# lipo-supply.net
KiCad netlist of a schematic drawn in Altium Designer
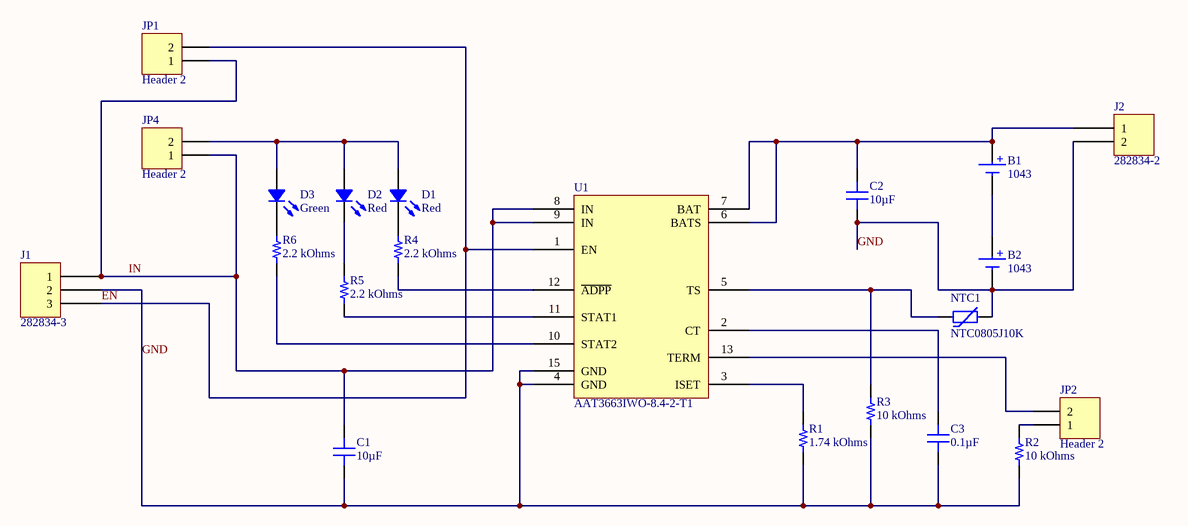
[diagram p0: lipo-supply.SchDoc]

(export (version "E")
  (design (tool "Eeschema 10.0.6"))
  (components
    (comp (ref "B1")
      (value "1043")
      (footprint "KEYSTONE 1043")
      (description "BATTERY HOLDER 18650 PC PIN")
      (fields (field (name "MANUFACTURER") "Keystone Electronics"))
      (libsource (lib "Celestial Altium Library - altium_library") (part "Keystone 1043"))
    )
    (comp (ref "B2")
      (value "1043")
      (footprint "KEYSTONE 1043")
      (description "BATTERY HOLDER 18650 PC PIN")
      (fields (field (name "MANUFACTURER") "Keystone Electronics"))
      (libsource (lib "Celestial Altium Library - altium_library") (part "Keystone 1043"))
    )
    (comp (ref "C1")
      (value "10µF")
      (footprint "CAP 1210_3225 - 2.8MM")
      (description "CAP CER 10UF 25V X7R 1210 EPOXY")
      (fields
        (field (name "PART NUMBER") "GCG32ER71E106KA12L")
        (field (name "MANUFACTURER") "Murata Electronics")
      )
      (libsource (lib "Celestial Altium Library - altium_library") (part "Capacitor"))
    )
    (comp (ref "C2")
      (value "10µF")
      (footprint "CAP 0805_2012")
      (description "CAP CER 10UF 16V X7R 0805")
      (fields (field (name "PART NUMBER") "EMK212BB7106MG-T") (field (name "MANUFACTURER") "Taiyo Yuden"))
      (libsource (lib "Celestial Altium Library - altium_library") (part "Capacitor"))
    )
    (comp (ref "C3")
      (value "0.1µF")
      (footprint "CAP 0805_2012")
      (description "CAP CER 0.1UF 16V X7R 0805")
      (fields
        (field (name "PART NUMBER") "0805B104K160CT")
        (field (name "MANUFACTURER") "Walsin Technology Corporation")
      )
      (libsource (lib "Celestial Altium Library - altium_library") (part "Capacitor"))
    )
    (comp (ref "D1")
      (value "Red")
      (footprint "LED 0805_2012 RED")
      (description "LED RED 0805 SMD")
      (fields (field (name "PART NUMBER") "5990110007F") (field (name "MANUFACTURER") "Dialight"))
      (libsource (lib "Celestial Altium Library - altium_library") (part "LED"))
    )
    (comp (ref "D2")
      (value "Red")
      (footprint "LED 0805_2012 RED")
      (description "LED RED 0805 SMD")
      (fields (field (name "PART NUMBER") "5990110007F") (field (name "MANUFACTURER") "Dialight"))
      (libsource (lib "Celestial Altium Library - altium_library") (part "LED"))
    )
    (comp (ref "D3")
      (value "Green")
      (footprint "LED 0805_2012 GREEN")
      (description "LED GREEN 0805 SMD")
      (fields (field (name "PART NUMBER") "5975316507F") (field (name "MANUFACTURER") "Dialight"))
      (libsource (lib "Celestial Altium Library - altium_library") (part "LED"))
    )
    (comp (ref "J1")
      (value "282834-3")
      (footprint "TE 282834-3")
      (description "TERM BLK 3P SIDE ENT 2.54MM PCB")
      (fields (field (name "MANUFACTURER") "TE Connectivity AMP Connectors") (field (name "VOLTAGE") "150V"))
      (libsource (lib "Celestial Altium Library - altium_library") (part "3 Pin"))
    )
    (comp (ref "J2")
      (value "282834-2")
      (footprint "TE 282834-2")
      (description "TERM BLK 2P SIDE ENT 2.54MM PCB")
      (fields (field (name "MANUFACTURER") "TE Connectivity AMP Connectors") (field (name "VOLTAGE") "150V"))
      (libsource (lib "Celestial Altium Library - altium_library") (part "2 Pin"))
    )
    (comp (ref "JP1")
      (value "Header 2")
      (footprint "HDR1X2")
      (description "Header, 2-Pin")
      (fields (field (name "PUBLISHER") "Altium Limited"))
      (libsource (lib "") (part "Header 2_1"))
    )
    (comp (ref "JP2")
      (value "Header 2")
      (footprint "HDR1X2")
      (description "Header, 2-Pin")
      (fields (field (name "PUBLISHER") "Altium Limited"))
      (libsource (lib "Miscellaneous Connectors") (part "Header 2"))
    )
    (comp (ref "JP4")
      (value "Header 2")
      (footprint "HDR1X2")
      (description "Header, 2-Pin")
      (fields (field (name "PUBLISHER") "Altium Limited"))
      (libsource (lib "") (part "Header 2_1"))
    )
    (comp (ref "NTC1")
      (value "NTC0805J10K")
      (footprint "NTC 0805_2012")
      (description "THERMISTOR NTC 10KOHM 0805")
      (fields (field (name "MANUFACTURER") "TE Connectivity Passive Product"))
      (libsource (lib "Celestial Altium Library - altium_library") (part "Thermistor"))
    )
    (comp (ref "R1")
      (value "1.74 kOhms")
      (footprint "RES 0805_2012")
      (description "RES SMD 1.74K OHM 1% 1/8W 0805")
      (fields (field (name "PART NUMBER") "KTR10EZPF1741") (field (name "MANUFACTURER") "Rohm Semiconductor"))
      (libsource (lib "Celestial Altium Library - altium_library") (part "Resistor"))
    )
    (comp (ref "R2")
      (value "10 kOhms")
      (footprint "RES 0805_2012")
      (description "RES SMD 10K OHM 0.5% 1/8W 0805")
      (fields (field (name "PART NUMBER") "RT0805DRD0710KL") (field (name "MANUFACTURER") "Yageo"))
      (libsource (lib "Celestial Altium Library - altium_library") (part "Resistor"))
    )
    (comp (ref "R3")
      (value "10 kOhms")
      (footprint "RES 0805_2012")
      (description "RES SMD 10K OHM 0.5% 1/8W 0805")
      (fields (field (name "PART NUMBER") "RT0805DRD0710KL") (field (name "MANUFACTURER") "Yageo"))
      (libsource (lib "Celestial Altium Library - altium_library") (part "Resistor"))
    )
    (comp (ref "R4")
      (value "2.2 kOhms")
      (footprint "RES 0805_2012")
      (description "RES SMD 2.2K OHM 5% 1/4W 0805")
      (fields (field (name "PART NUMBER") "SR0805JR-7W2K2L") (field (name "MANUFACTURER") "Yageo"))
      (libsource (lib "Celestial Altium Library - altium_library") (part "Resistor"))
    )
    (comp (ref "R5")
      (value "2.2 kOhms")
      (footprint "RES 0805_2012")
      (description "RES SMD 2.2K OHM 5% 1/4W 0805")
      (fields (field (name "PART NUMBER") "SR0805JR-7W2K2L") (field (name "MANUFACTURER") "Yageo"))
      (libsource (lib "Celestial Altium Library - altium_library") (part "Resistor"))
    )
    (comp (ref "R6")
      (value "2.2 kOhms")
      (footprint "RES 0805_2012")
      (description "RES SMD 2.2K OHM 5% 1/4W 0805")
      (fields (field (name "PART NUMBER") "SR0805JR-7W2K2L") (field (name "MANUFACTURER") "Yageo"))
      (libsource (lib "Celestial Altium Library - altium_library") (part "Resistor"))
    )
    (comp (ref "U1")
      (value "AAT3663IWO-8.4-2-T1")
      (footprint "SKYWORKS TDFN-14 3X3MM")
      (description "IC LI-ION CHARGER 14-DFN")
      (fields (field (name "MANUFACTURER") "Skyworks Solutions Inc."))
      (libsource (lib "Celestial Altium Library - altium_library") (part "SKYWORKS AAT3663"))
    )
  )
  (nets
    (net (code "1") (name "/EN") (class "Default")
      (node (ref "J1") (pin "3") (pinfunction "3_3") (pintype "passive"))
      (node (ref "JP1") (pin "2") (pinfunction "2_2") (pintype "passive"))
      (node (ref "U1") (pin "1") (pinfunction "EN_1") (pintype "passive"))
    )
    (net (code "2") (name "/GND") (class "Default")
      (node (ref "B2") (pin "2") (pinfunction "-_2") (pintype "passive"))
      (node (ref "C1") (pin "1") (pinfunction "1_1") (pintype "passive"))
      (node (ref "C2") (pin "1") (pinfunction "1_1") (pintype "passive"))
      (node (ref "C3") (pin "1") (pinfunction "1_1") (pintype "passive"))
      (node (ref "J1") (pin "2") (pinfunction "2_2") (pintype "passive"))
      (node (ref "J2") (pin "2") (pinfunction "2_2") (pintype "passive"))
      (node (ref "NTC1") (pin "2") (pinfunction "2_2") (pintype "passive"))
      (node (ref "R1") (pin "1") (pinfunction "1_1") (pintype "passive"))
      (node (ref "R2") (pin "1") (pinfunction "1_1") (pintype "passive"))
      (node (ref "R3") (pin "1") (pinfunction "1_1") (pintype "passive"))
      (node (ref "U1") (pin "15") (pinfunction "GND_15") (pintype "passive"))
      (node (ref "U1") (pin "4") (pinfunction "GND_4") (pintype "passive"))
    )
    (net (code "3") (name "/IN") (class "Default")
      (node (ref "C1") (pin "2") (pinfunction "2_2") (pintype "passive"))
      (node (ref "J1") (pin "1") (pinfunction "1_1") (pintype "passive"))
      (node (ref "JP1") (pin "1") (pinfunction "1_1") (pintype "passive"))
      (node (ref "JP4") (pin "1") (pinfunction "1_1") (pintype "passive"))
      (node (ref "U1") (pin "8") (pinfunction "IN_8") (pintype "passive"))
      (node (ref "U1") (pin "9") (pinfunction "IN_9") (pintype "passive"))
    )
    (net (code "4") (name "Net-(B1-+)") (class "Default")
      (node (ref "B1") (pin "1") (pinfunction "+_1") (pintype "passive"))
      (node (ref "C2") (pin "2") (pinfunction "2_2") (pintype "passive"))
      (node (ref "J2") (pin "1") (pinfunction "1_1") (pintype "passive"))
      (node (ref "U1") (pin "6") (pinfunction "BATS_6") (pintype "passive"))
      (node (ref "U1") (pin "7") (pinfunction "BAT_7") (pintype "passive"))
    )
    (net (code "5") (name "Net-(B1--)") (class "Default")
      (node (ref "B1") (pin "2") (pinfunction "-_2") (pintype "passive"))
      (node (ref "B2") (pin "1") (pinfunction "+_1") (pintype "passive"))
    )
    (net (code "6") (name "Net-(D1-Pad1)") (class "Default")
      (node (ref "D1") (pin "1") (pinfunction "1_1") (pintype "passive"))
      (node (ref "D2") (pin "1") (pinfunction "1_1") (pintype "passive"))
      (node (ref "D3") (pin "1") (pinfunction "1_1") (pintype "passive"))
      (node (ref "JP4") (pin "2") (pinfunction "2_2") (pintype "passive"))
    )
    (net (code "7") (name "Net-(D1-Pad2)") (class "Default")
      (node (ref "D1") (pin "2") (pinfunction "2_2") (pintype "passive"))
      (node (ref "R4") (pin "2") (pinfunction "2_2") (pintype "passive"))
    )
    (net (code "8") (name "Net-(D2-Pad2)") (class "Default")
      (node (ref "D2") (pin "2") (pinfunction "2_2") (pintype "passive"))
      (node (ref "R5") (pin "2") (pinfunction "2_2") (pintype "passive"))
    )
    (net (code "9") (name "Net-(D3-Pad2)") (class "Default")
      (node (ref "D3") (pin "2") (pinfunction "2_2") (pintype "passive"))
      (node (ref "R6") (pin "2") (pinfunction "2_2") (pintype "passive"))
    )
    (net (code "10") (name "Net-(JP2-Pad1)") (class "Default")
      (node (ref "JP2") (pin "1") (pinfunction "1_1") (pintype "passive"))
      (node (ref "R2") (pin "2") (pinfunction "2_2") (pintype "passive"))
    )
    (net (code "11") (name "Net-(U1-CT)") (class "Default")
      (node (ref "C3") (pin "2") (pinfunction "2_2") (pintype "passive"))
      (node (ref "U1") (pin "2") (pinfunction "CT_2") (pintype "passive"))
    )
    (net (code "12") (name "Net-(U1-ISET)") (class "Default")
      (node (ref "R1") (pin "2") (pinfunction "2_2") (pintype "passive"))
      (node (ref "U1") (pin "3") (pinfunction "ISET_3") (pintype "passive"))
    )
    (net (code "13") (name "Net-(U1-STAT1)") (class "Default")
      (node (ref "R5") (pin "1") (pinfunction "1_1") (pintype "passive"))
      (node (ref "U1") (pin "11") (pinfunction "STAT1_11") (pintype "passive"))
    )
    (net (code "14") (name "Net-(U1-STAT2)") (class "Default")
      (node (ref "R6") (pin "1") (pinfunction "1_1") (pintype "passive"))
      (node (ref "U1") (pin "10") (pinfunction "STAT2_10") (pintype "passive"))
    )
    (net (code "15") (name "Net-(U1-TERM)") (class "Default")
      (node (ref "JP2") (pin "2") (pinfunction "2_2") (pintype "passive"))
      (node (ref "U1") (pin "13") (pinfunction "TERM_13") (pintype "passive"))
    )
    (net (code "16") (name "Net-(U1-TS)") (class "Default")
      (node (ref "NTC1") (pin "1") (pinfunction "1_1") (pintype "passive"))
      (node (ref "R3") (pin "2") (pinfunction "2_2") (pintype "passive"))
      (node (ref "U1") (pin "5") (pinfunction "TS_5") (pintype "passive"))
    )
    (net (code "17") (name "Net-(U1-~{ADPP})") (class "Default")
      (node (ref "R4") (pin "1") (pinfunction "1_1") (pintype "passive"))
      (node (ref "U1") (pin "12") (pinfunction "~{ADPP}_12") (pintype "passive"))
    )
  )
)
